# R2020Interface-RS485.net
KiCad netlist of a schematic drawn in EAGLE
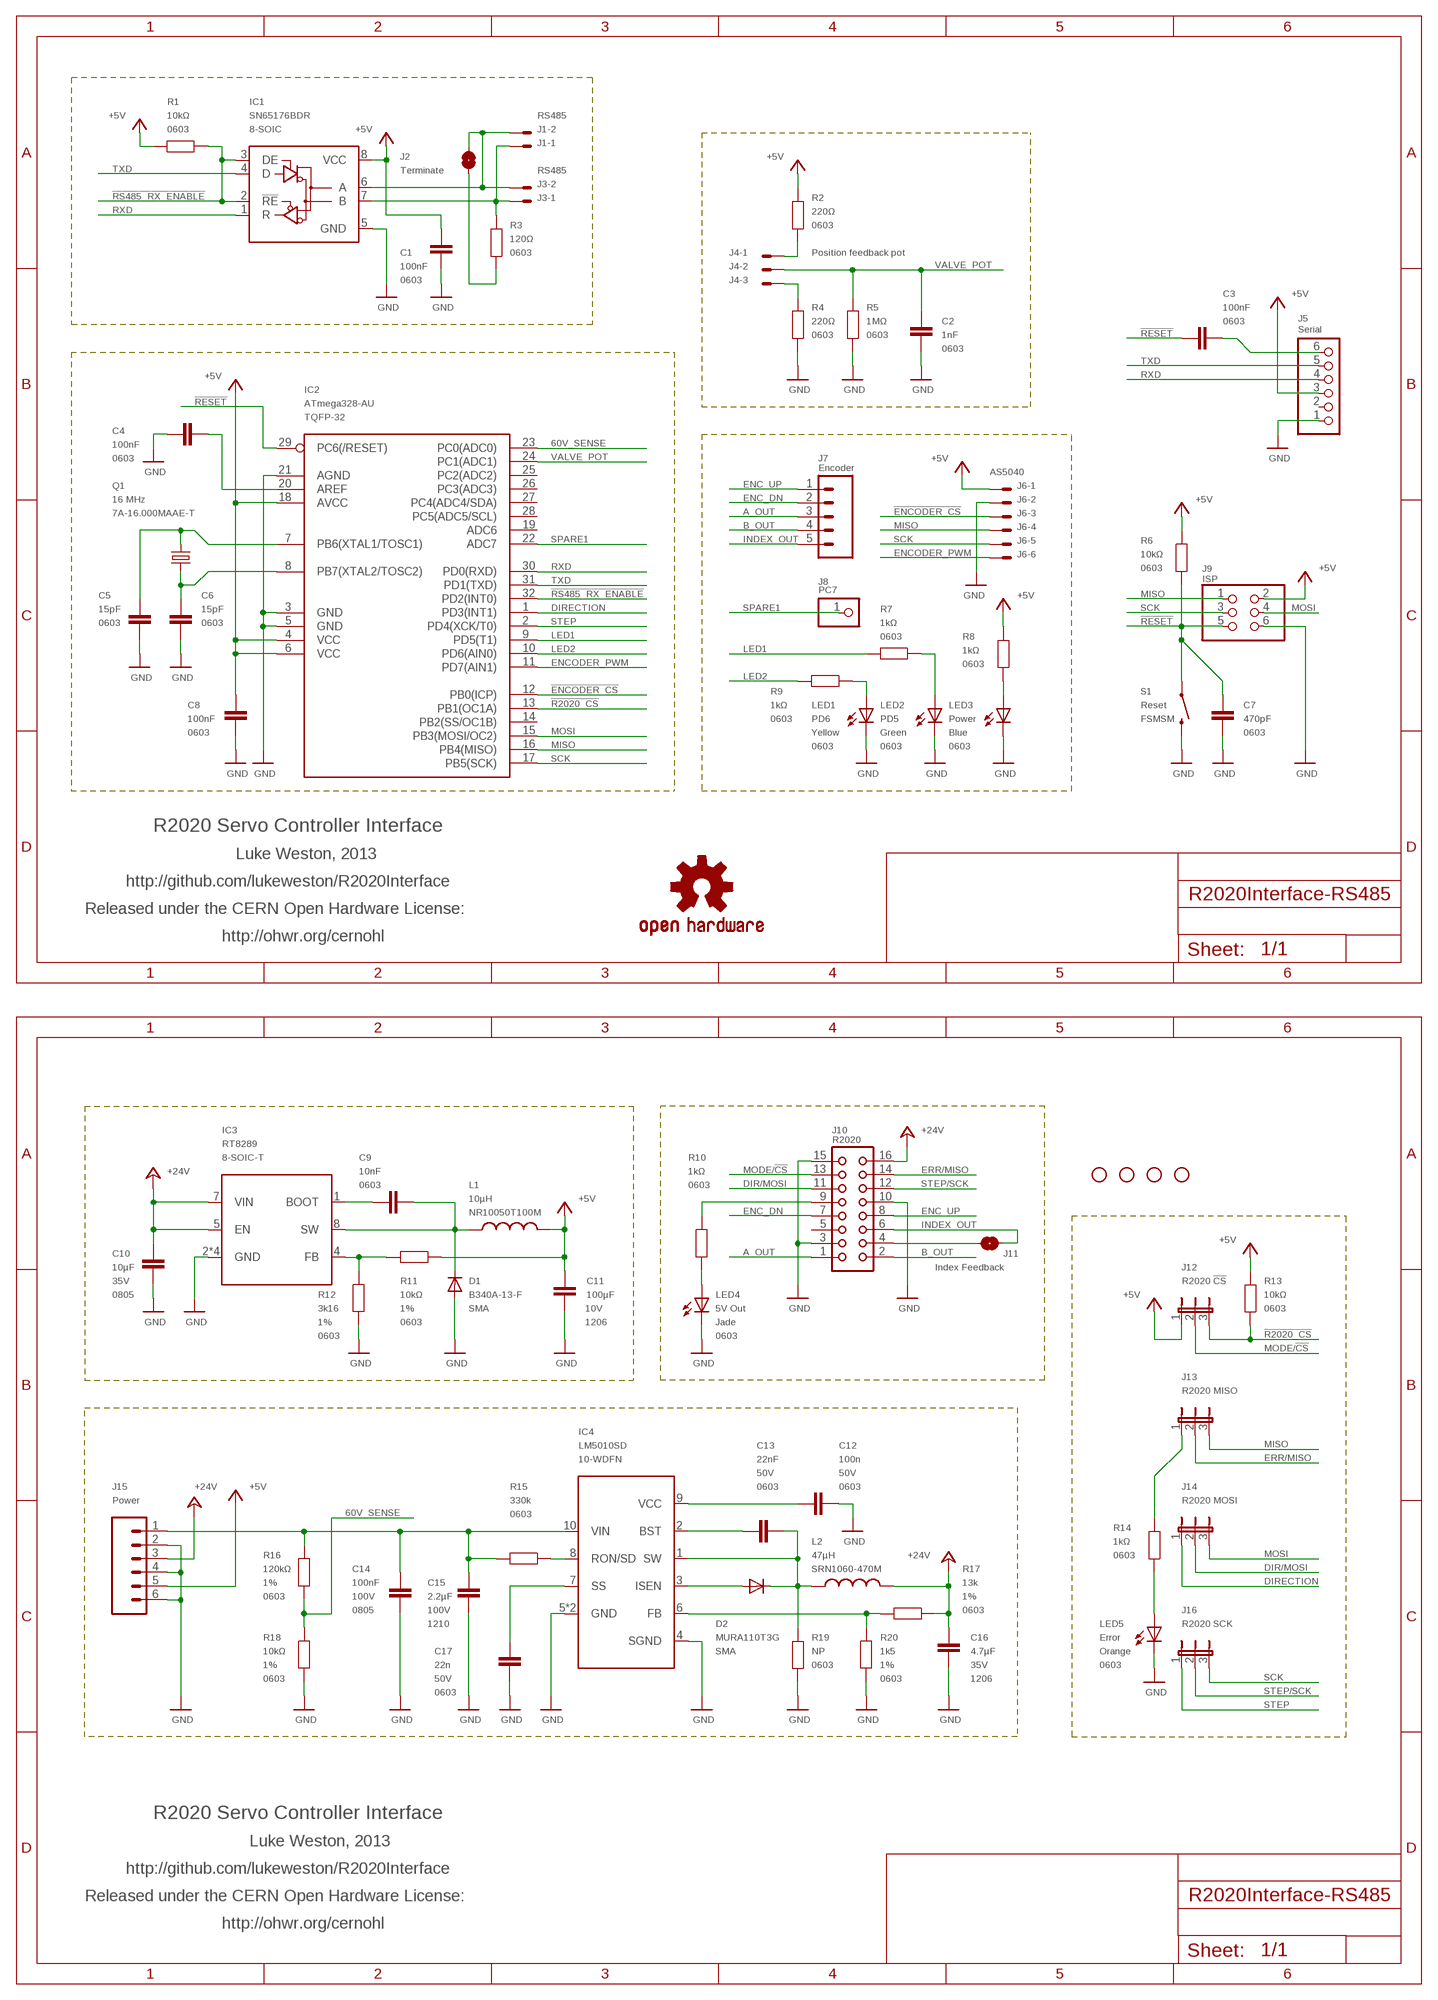
[diagram p0: schematic, sheet 1]

(export (version "E")
  (design (tool "Eeschema 10.0.6"))
  (components
    (comp (ref "C1")
      (value "100nF")
      (footprint "eagle-import:0603")
      (fields (field (name "PACKAGE") "0603"))
      (libsource (lib "eagle-import") (part "CAP0603"))
    )
    (comp (ref "C2")
      (value "1nF")
      (footprint "eagle-import:0603")
      (fields (field (name "PACKAGE") "0603"))
      (libsource (lib "eagle-import") (part "CAP0603"))
    )
    (comp (ref "C3")
      (value "100nF")
      (footprint "eagle-import:0603")
      (fields (field (name "PACKAGE") "0603"))
      (libsource (lib "eagle-import") (part "CAP0603"))
    )
    (comp (ref "C4")
      (value "100nF")
      (footprint "eagle-import:0603")
      (fields (field (name "PACKAGE") "0603"))
      (libsource (lib "eagle-import") (part "CAP0603"))
    )
    (comp (ref "C5")
      (value "15pF")
      (footprint "eagle-import:0603")
      (fields (field (name "PACKAGE") "0603"))
      (libsource (lib "eagle-import") (part "CAP0603"))
    )
    (comp (ref "C6")
      (value "15pF")
      (footprint "eagle-import:0603")
      (fields (field (name "PACKAGE") "0603"))
      (libsource (lib "eagle-import") (part "CAP0603"))
    )
    (comp (ref "C7")
      (value "470pF")
      (footprint "eagle-import:0603")
      (fields (field (name "PACKAGE") "0603"))
      (libsource (lib "eagle-import") (part "CAP0603"))
    )
    (comp (ref "C8")
      (value "100nF")
      (footprint "eagle-import:0603")
      (fields (field (name "PACKAGE") "0603"))
      (libsource (lib "eagle-import") (part "CAP0603"))
    )
    (comp (ref "C9")
      (value "10nF")
      (footprint "eagle-import:0603")
      (fields (field (name "PACKAGE") "0603"))
      (libsource (lib "eagle-import") (part "CAP0603"))
    )
    (comp (ref "C10")
      (value "10µF")
      (footprint "eagle-import:0805")
      (fields (field (name "PACKAGE") "0805") (field (name "VOLTAGE") "35V"))
      (libsource (lib "eagle-import") (part "CAP0805"))
    )
    (comp (ref "C11")
      (value "100µF")
      (footprint "eagle-import:C1206K")
      (fields (field (name "PACKAGE") "1206") (field (name "VOLTAGE") "10V"))
      (libsource (lib "eagle-import") (part "C-EUC1206K"))
    )
    (comp (ref "C12")
      (value "100n")
      (footprint "eagle-import:0603")
      (fields (field (name "PACKAGE") "0603") (field (name "VOLTAGE") "50V"))
      (libsource (lib "eagle-import") (part "CAP0603"))
    )
    (comp (ref "C13")
      (value "22nF")
      (footprint "eagle-import:0603")
      (fields (field (name "PACKAGE") "0603") (field (name "VOLTAGE") "50V"))
      (libsource (lib "eagle-import") (part "CAP0603"))
    )
    (comp (ref "C14")
      (value "100nF")
      (footprint "eagle-import:0805")
      (fields (field (name "PACKAGE") "0805") (field (name "VOLTAGE") "100V"))
      (libsource (lib "eagle-import") (part "CAP0805"))
    )
    (comp (ref "C15")
      (value "2.2µF")
      (footprint "eagle-import:C1210K")
      (fields (field (name "PACKAGE") "1210") (field (name "VOLTAGE") "100V"))
      (libsource (lib "eagle-import") (part "C-EUC1210K"))
    )
    (comp (ref "C16")
      (value "4.7µF")
      (footprint "eagle-import:C1206K")
      (fields (field (name "PACKAGE") "1206") (field (name "VOLTAGE") "35V"))
      (libsource (lib "eagle-import") (part "C-EUC1206K"))
    )
    (comp (ref "C17")
      (value "22n")
      (footprint "eagle-import:0603")
      (fields (field (name "PACKAGE") "0603") (field (name "VOLTAGE") "50V"))
      (libsource (lib "eagle-import") (part "CAP0603"))
    )
    (comp (ref "D1")
      (value "B340A-13-F")
      (footprint "eagle-import:SMA-DIODE")
      (fields (field (name "PACKAGE") "SMA"))
      (libsource (lib "eagle-import") (part "DIODESMA"))
    )
    (comp (ref "D2")
      (value "MURA110T3G")
      (footprint "eagle-import:SMA-DIODE")
      (fields (field (name "PACKAGE") "SMA"))
      (libsource (lib "eagle-import") (part "DIODESMA"))
    )
    (comp (ref "IC1")
      (value "SN65176BDR")
      (footprint "eagle-import:D_R-PDSO-G8")
      (fields (field (name "PACKAGE") "8-SOIC"))
      (libsource (lib "eagle-import") (part "75176AD"))
    )
    (comp (ref "IC2")
      (value "ATmega328-AU")
      (footprint "eagle-import:TQFP32-08")
      (fields (field (name "PACKAGE") "TQFP-32"))
      (libsource (lib "eagle-import") (part "AVR-MEGA8-AI"))
    )
    (comp (ref "IC3")
      (value "RT8289")
      (footprint "eagle-import:SO08T")
      (fields (field (name "PACKAGE") "8-SOIC-T"))
      (libsource (lib "eagle-import") (part "RT8289"))
    )
    (comp (ref "IC4")
      (value "LM5010SD")
      (footprint "eagle-import:10-WSON")
      (fields (field (name "PACKAGE") "10-WDFN"))
      (libsource (lib "eagle-import") (part "LM5010"))
    )
    (comp (ref "J1")
      (value "RS485")
      (footprint "eagle-import:7395-02")
      (libsource (lib "eagle-import") (part "22-?-0205-7028"))
    )
    (comp (ref "J2")
      (value "Terminate")
      (footprint "eagle-import:SJ")
      (libsource (lib "eagle-import") (part "SJ"))
    )
    (comp (ref "J3")
      (value "RS485")
      (footprint "eagle-import:7395-02")
      (fields (field (name "OC_FARNELL") "9731601") (field (name "OC_NEWARK") "unknown"))
      (libsource (lib "eagle-import") (part "22-?-0205-7028"))
    )
    (comp (ref "J4")
      (value "Position feedback pot")
      (footprint "eagle-import:7395-03")
      (libsource (lib "eagle-import") (part "22-?-0305-7038"))
    )
    (comp (ref "J5")
      (value "Serial")
      (footprint "eagle-import:1X06")
      (libsource (lib "eagle-import") (part "PINHD-1X6"))
    )
    (comp (ref "J6")
      (value "AS5040")
      (footprint "eagle-import:7395-06")
      (fields (field (name "OC_FARNELL") "unknown") (field (name "OC_NEWARK") "unknown"))
      (libsource (lib "eagle-import") (part "22-?-0605-7068"))
    )
    (comp (ref "J7")
      (value "Encoder")
      (footprint "eagle-import:1X05")
      (libsource (lib "eagle-import") (part "M05PTH"))
    )
    (comp (ref "J8")
      (value "PC7")
      (footprint "eagle-import:1X01")
      (libsource (lib "eagle-import") (part "PINHD-1X1"))
    )
    (comp (ref "J9")
      (value "ISP")
      (footprint "eagle-import:2X03")
      (libsource (lib "eagle-import") (part "PINHD-2X3"))
    )
    (comp (ref "J10")
      (value "R2020")
      (footprint "eagle-import:CON16")
      (fields (field (name "OC_FARNELL") "unknown") (field (name "OC_NEWARK") "unknown"))
      (libsource (lib "eagle-import") (part "CON16"))
    )
    (comp (ref "J11")
      (value "Index Feedback")
      (footprint "eagle-import:SJ")
      (libsource (lib "eagle-import") (part "SJ"))
    )
    (comp (ref "J12")
      (value "R2020 !CS")
      (footprint "eagle-import:JP2")
      (libsource (lib "eagle-import") (part "JP2E"))
    )
    (comp (ref "J13")
      (value "R2020 MISO")
      (footprint "eagle-import:JP2")
      (libsource (lib "eagle-import") (part "JP2E"))
    )
    (comp (ref "J14")
      (value "R2020 MOSI")
      (footprint "eagle-import:JP2")
      (libsource (lib "eagle-import") (part "JP2E"))
    )
    (comp (ref "J15")
      (value "Power")
      (footprint "eagle-import:TERMINALBLOCK_3.5MM_6")
      (libsource (lib "eagle-import") (part "M06"))
    )
    (comp (ref "J16")
      (value "R2020 SCK")
      (footprint "eagle-import:JP2")
      (libsource (lib "eagle-import") (part "JP2E"))
    )
    (comp (ref "JP1")
      (value "STAND-OFF")
      (footprint "eagle-import:STAND-OFF")
      (libsource (lib "eagle-import") (part "STAND-OFF"))
    )
    (comp (ref "JP2")
      (value "STAND-OFF")
      (footprint "eagle-import:STAND-OFF")
      (libsource (lib "eagle-import") (part "STAND-OFF"))
    )
    (comp (ref "JP3")
      (value "STAND-OFF")
      (footprint "eagle-import:STAND-OFF")
      (libsource (lib "eagle-import") (part "STAND-OFF"))
    )
    (comp (ref "JP4")
      (value "STAND-OFF")
      (footprint "eagle-import:STAND-OFF")
      (libsource (lib "eagle-import") (part "STAND-OFF"))
    )
    (comp (ref "L1")
      (value "10µH")
      (footprint "eagle-import:NR10050")
      (fields (field (name "ID") "NR10050T100M"))
      (libsource (lib "eagle-import") (part "NR10050"))
    )
    (comp (ref "L2")
      (value "47µH")
      (footprint "eagle-import:SRN1060")
      (fields (field (name "ID") "SRN1060-470M"))
      (libsource (lib "eagle-import") (part "SRN1060"))
    )
    (comp (ref "LED1")
      (value "PD6")
      (footprint "eagle-import:LED-0603")
      (fields (field (name "COLOR") "Yellow") (field (name "PACKAGE") "0603"))
      (libsource (lib "eagle-import") (part "LED0603"))
    )
    (comp (ref "LED2")
      (value "PD5")
      (footprint "eagle-import:LED-0603")
      (fields (field (name "COLOR") "Green") (field (name "PACKAGE") "0603"))
      (libsource (lib "eagle-import") (part "LED0603"))
    )
    (comp (ref "LED3")
      (value "Power")
      (footprint "eagle-import:LED-0603")
      (fields (field (name "COLOR") "Blue") (field (name "PACKAGE") "0603"))
      (libsource (lib "eagle-import") (part "LED0603"))
    )
    (comp (ref "LED4")
      (value "5V Out")
      (footprint "eagle-import:LED-0603")
      (fields (field (name "COLOR") "Jade") (field (name "PACKAGE") "0603"))
      (libsource (lib "eagle-import") (part "LED0603"))
    )
    (comp (ref "LED5")
      (value "Error")
      (footprint "eagle-import:LED-0603")
      (fields (field (name "COLOR") "Orange") (field (name "PACKAGE") "0603"))
      (libsource (lib "eagle-import") (part "LED0603"))
    )
    (comp (ref "Q1")
      (value "16 MHz")
      (footprint "eagle-import:CRYSTAL-3.2X5MM")
      (fields (field (name "ID") "7A-16.000MAAE-T"))
      (libsource (lib "eagle-import") (part "CRYSTAL-2LEAD3.2X5"))
    )
    (comp (ref "R1")
      (value "10kΩ")
      (footprint "eagle-import:0603")
      (fields (field (name "PACKAGE") "0603"))
      (libsource (lib "eagle-import") (part "RESISTOR0603"))
    )
    (comp (ref "R2")
      (value "220Ω")
      (footprint "eagle-import:0603")
      (fields (field (name "PACKAGE") "0603"))
      (libsource (lib "eagle-import") (part "RESISTOR0603"))
    )
    (comp (ref "R3")
      (value "120Ω")
      (footprint "eagle-import:0603")
      (fields (field (name "PACKAGE") "0603"))
      (libsource (lib "eagle-import") (part "RESISTOR0603"))
    )
    (comp (ref "R4")
      (value "220Ω")
      (footprint "eagle-import:0603")
      (fields (field (name "PACKAGE") "0603"))
      (libsource (lib "eagle-import") (part "RESISTOR0603"))
    )
    (comp (ref "R5")
      (value "1MΩ")
      (footprint "eagle-import:0603")
      (fields (field (name "PACKAGE") "0603"))
      (libsource (lib "eagle-import") (part "RESISTOR0603"))
    )
    (comp (ref "R6")
      (value "10kΩ")
      (footprint "eagle-import:0603")
      (fields (field (name "PACKAGE") "0603"))
      (libsource (lib "eagle-import") (part "RESISTOR0603"))
    )
    (comp (ref "R7")
      (value "1kΩ")
      (footprint "eagle-import:0603")
      (fields (field (name "PACKAGE") "0603"))
      (libsource (lib "eagle-import") (part "RESISTOR0603"))
    )
    (comp (ref "R8")
      (value "1kΩ")
      (footprint "eagle-import:0603")
      (fields (field (name "PACKAGE") "0603"))
      (libsource (lib "eagle-import") (part "RESISTOR0603"))
    )
    (comp (ref "R9")
      (value "1kΩ")
      (footprint "eagle-import:0603")
      (fields (field (name "PACKAGE") "0603"))
      (libsource (lib "eagle-import") (part "RESISTOR0603"))
    )
    (comp (ref "R10")
      (value "1kΩ")
      (footprint "eagle-import:0603")
      (fields (field (name "PACKAGE") "0603"))
      (libsource (lib "eagle-import") (part "RESISTOR0603"))
    )
    (comp (ref "R11")
      (value "10kΩ")
      (footprint "eagle-import:0603")
      (fields (field (name "PACKAGE") "0603") (field (name "TOLERANCE") "1%"))
      (libsource (lib "eagle-import") (part "RESISTOR0603"))
    )
    (comp (ref "R12")
      (value "3k16")
      (footprint "eagle-import:0603")
      (fields (field (name "PACKAGE") "0603") (field (name "TOLERANCE") "1%"))
      (libsource (lib "eagle-import") (part "RESISTOR0603"))
    )
    (comp (ref "R13")
      (value "10kΩ")
      (footprint "eagle-import:0603")
      (fields (field (name "PACKAGE") "0603"))
      (libsource (lib "eagle-import") (part "RESISTOR0603"))
    )
    (comp (ref "R14")
      (value "1kΩ")
      (footprint "eagle-import:0603")
      (fields (field (name "PACKAGE") "0603"))
      (libsource (lib "eagle-import") (part "RESISTOR0603"))
    )
    (comp (ref "R15")
      (value "330k")
      (footprint "eagle-import:0603")
      (fields (field (name "PACKAGE") "0603"))
      (libsource (lib "eagle-import") (part "RESISTOR0603"))
    )
    (comp (ref "R16")
      (value "120kΩ")
      (footprint "eagle-import:0603")
      (fields (field (name "PACKAGE") "0603") (field (name "TOLERANCE") "1%"))
      (libsource (lib "eagle-import") (part "RESISTOR0603"))
    )
    (comp (ref "R17")
      (value "13k")
      (footprint "eagle-import:0603")
      (fields (field (name "PACKAGE") "0603") (field (name "TOLERANCE") "1%"))
      (libsource (lib "eagle-import") (part "RESISTOR0603"))
    )
    (comp (ref "R18")
      (value "10kΩ")
      (footprint "eagle-import:0603")
      (fields (field (name "PACKAGE") "0603") (field (name "TOLERANCE") "1%"))
      (libsource (lib "eagle-import") (part "RESISTOR0603"))
    )
    (comp (ref "R19")
      (value "NP")
      (footprint "eagle-import:0603")
      (fields (field (name "PACKAGE") "0603"))
      (libsource (lib "eagle-import") (part "RESISTOR0603"))
    )
    (comp (ref "R20")
      (value "1k5")
      (footprint "eagle-import:0603")
      (fields (field (name "PACKAGE") "0603") (field (name "TOLERANCE") "1%"))
      (libsource (lib "eagle-import") (part "RESISTOR0603"))
    )
    (comp (ref "S1")
      (value "Reset")
      (footprint "eagle-import:FSMSM")
      (fields (field (name "PACKAGE") "FSMSM"))
      (libsource (lib "eagle-import") (part "FSMSM"))
    )
    (comp (ref "SY1")
      (value "OSHW-LOGOS")
      (footprint "eagle-import:OSHW-LOGO-S")
      (libsource (lib "eagle-import") (part "OSHW-LOGOS"))
    )
  )
  (nets
    (net (code "1") (name "+5V") (class "Default")
      (node (ref "C1") (pin "2") (pinfunction "2_2") (pintype "passive"))
      (node (ref "C11") (pin "1") (pinfunction "1_1") (pintype "passive"))
      (node (ref "C8") (pin "1") (pinfunction "1_1") (pintype "passive"))
      (node (ref "IC1") (pin "8") (pinfunction "VCC_8") (pintype "power_in"))
      (node (ref "IC2") (pin "18") (pinfunction "AVCC_18") (pintype "bidirectional"))
      (node (ref "IC2") (pin "4") (pinfunction "VCC_4") (pintype "bidirectional"))
      (node (ref "IC2") (pin "6") (pinfunction "VCC_6") (pintype "bidirectional"))
      (node (ref "J12") (pin "1") (pinfunction "1_1") (pintype "passive"))
      (node (ref "J15") (pin "5") (pinfunction "5_5") (pintype "passive"))
      (node (ref "J5") (pin "3") (pinfunction "3_3") (pintype "passive"))
      (node (ref "J6") (pin "1") (pinfunction "S_1") (pintype "passive"))
      (node (ref "J9") (pin "2") (pinfunction "2_2") (pintype "passive"))
      (node (ref "L1") (pin "2") (pinfunction "2_2") (pintype "bidirectional"))
      (node (ref "R1") (pin "1") (pinfunction "1_1") (pintype "passive"))
      (node (ref "R11") (pin "1") (pinfunction "1_1") (pintype "passive"))
      (node (ref "R13") (pin "1") (pinfunction "1_1") (pintype "passive"))
      (node (ref "R2") (pin "1") (pinfunction "1_1") (pintype "passive"))
      (node (ref "R6") (pin "2") (pinfunction "2_2") (pintype "passive"))
      (node (ref "R8") (pin "1") (pinfunction "1_1") (pintype "passive"))
    )
    (net (code "2") (name "+24V") (class "Default")
      (node (ref "C10") (pin "2") (pinfunction "2_2") (pintype "passive"))
      (node (ref "C16") (pin "1") (pinfunction "1_1") (pintype "passive"))
      (node (ref "IC3") (pin "5") (pinfunction "EN_5") (pintype "bidirectional"))
      (node (ref "IC3") (pin "7") (pinfunction "VIN_7") (pintype "bidirectional"))
      (node (ref "J10") (pin "16") (pinfunction "16_16") (pintype "passive"))
      (node (ref "J15") (pin "3") (pinfunction "3_3") (pintype "passive"))
      (node (ref "L2") (pin "2") (pinfunction "2_2") (pintype "bidirectional"))
      (node (ref "R17") (pin "1") (pinfunction "1_1") (pintype "passive"))
    )
    (net (code "3") (name "/60V_SENSE") (class "Default")
      (node (ref "IC2") (pin "23") (pinfunction "PC0(ADC0)_23") (pintype "bidirectional"))
      (node (ref "R16") (pin "1") (pinfunction "1_1") (pintype "passive"))
      (node (ref "R18") (pin "2") (pinfunction "2_2") (pintype "passive"))
    )
    (net (code "4") (name "/A_OUT") (class "Default")
      (node (ref "J10") (pin "1") (pinfunction "1_1") (pintype "passive"))
      (node (ref "J7") (pin "3") (pinfunction "3_3") (pintype "passive"))
    )
    (net (code "5") (name "/B_OUT") (class "Default")
      (node (ref "J10") (pin "2") (pinfunction "2_2") (pintype "passive"))
      (node (ref "J7") (pin "4") (pinfunction "4_4") (pintype "passive"))
    )
    (net (code "6") (name "/DIRECTION") (class "Default")
      (node (ref "IC2") (pin "1") (pinfunction "PD3(INT1)_1") (pintype "bidirectional"))
      (node (ref "J14") (pin "1") (pinfunction "1_1") (pintype "passive"))
    )
    (net (code "7") (name "/DIR{slash}MOSI") (class "Default")
      (node (ref "J10") (pin "11") (pinfunction "11_11") (pintype "passive"))
      (node (ref "J14") (pin "2") (pinfunction "2_2") (pintype "passive"))
    )
    (net (code "8") (name "/ENCODER_PWM") (class "Default")
      (node (ref "IC2") (pin "11") (pinfunction "PD7(AIN1)_11") (pintype "bidirectional"))
      (node (ref "J6") (pin "6") (pinfunction "S_6") (pintype "passive"))
    )
    (net (code "9") (name "/ENC_DN") (class "Default")
      (node (ref "J10") (pin "7") (pinfunction "7_7") (pintype "passive"))
      (node (ref "J7") (pin "2") (pinfunction "2_2") (pintype "passive"))
    )
    (net (code "10") (name "/ENC_UP") (class "Default")
      (node (ref "J10") (pin "8") (pinfunction "8_8") (pintype "passive"))
      (node (ref "J7") (pin "1") (pinfunction "1_1") (pintype "passive"))
    )
    (net (code "11") (name "/ERR{slash}MISO") (class "Default")
      (node (ref "J10") (pin "14") (pinfunction "14_14") (pintype "passive"))
      (node (ref "J13") (pin "2") (pinfunction "2_2") (pintype "passive"))
    )
    (net (code "12") (name "/INDEX_OUT") (class "Default")
      (node (ref "J10") (pin "6") (pinfunction "6_6") (pintype "passive"))
      (node (ref "J11") (pin "1") (pinfunction "1_1") (pintype "passive"))
      (node (ref "J7") (pin "5") (pinfunction "5_5") (pintype "passive"))
    )
    (net (code "13") (name "/LED1") (class "Default")
      (node (ref "IC2") (pin "9") (pinfunction "PD5(T1)_9") (pintype "bidirectional"))
      (node (ref "R7") (pin "2") (pinfunction "2_2") (pintype "passive"))
    )
    (net (code "14") (name "/LED2") (class "Default")
      (node (ref "IC2") (pin "10") (pinfunction "PD6(AIN0)_10") (pintype "bidirectional"))
      (node (ref "R9") (pin "2") (pinfunction "2_2") (pintype "passive"))
    )
    (net (code "15") (name "/MISO") (class "Default")
      (node (ref "IC2") (pin "16") (pinfunction "PB4(MISO)_16") (pintype "bidirectional"))
      (node (ref "J13") (pin "3") (pinfunction "3_3") (pintype "passive"))
      (node (ref "J6") (pin "4") (pinfunction "S_4") (pintype "passive"))
      (node (ref "J9") (pin "1") (pinfunction "1_1") (pintype "passive"))
    )
    (net (code "16") (name "/MODE{slash}~{CS}") (class "Default")
      (node (ref "J10") (pin "13") (pinfunction "13_13") (pintype "passive"))
      (node (ref "J12") (pin "2") (pinfunction "2_2") (pintype "passive"))
    )
    (net (code "17") (name "/MOSI") (class "Default")
      (node (ref "IC2") (pin "15") (pinfunction "PB3(MOSI/OC2)_15") (pintype "bidirectional"))
      (node (ref "J14") (pin "3") (pinfunction "3_3") (pintype "passive"))
      (node (ref "J9") (pin "4") (pinfunction "4_4") (pintype "passive"))
    )
    (net (code "18") (name "/RXD") (class "Default")
      (node (ref "IC1") (pin "1") (pinfunction "R_1") (pintype "input"))
      (node (ref "IC2") (pin "30") (pinfunction "PD0(RXD)_30") (pintype "bidirectional"))
      (node (ref "J5") (pin "4") (pinfunction "4_4") (pintype "passive"))
    )
    (net (code "19") (name "/SCK") (class "Default")
      (node (ref "IC2") (pin "17") (pinfunction "PB5(SCK)_17") (pintype "bidirectional"))
      (node (ref "J16") (pin "3") (pinfunction "3_3") (pintype "passive"))
      (node (ref "J6") (pin "5") (pinfunction "S_5") (pintype "passive"))
      (node (ref "J9") (pin "3") (pinfunction "3_3") (pintype "passive"))
    )
    (net (code "20") (name "/SPARE1") (class "Default")
      (node (ref "IC2") (pin "22") (pinfunction "ADC7_22") (pintype "bidirectional"))
      (node (ref "J8") (pin "1") (pinfunction "1_1") (pintype "passive"))
    )
    (net (code "21") (name "/STEP") (class "Default")
      (node (ref "IC2") (pin "2") (pinfunction "PD4(XCK/T0)_2") (pintype "bidirectional"))
      (node (ref "J16") (pin "1") (pinfunction "1_1") (pintype "passive"))
    )
    (net (code "22") (name "/STEP{slash}SCK") (class "Default")
      (node (ref "J10") (pin "12") (pinfunction "12_12") (pintype "passive"))
      (node (ref "J16") (pin "2") (pinfunction "2_2") (pintype "passive"))
    )
    (net (code "23") (name "/TXD") (class "Default")
      (node (ref "IC1") (pin "4") (pinfunction "D_4") (pintype "input"))
      (node (ref "IC2") (pin "31") (pinfunction "PD1(TXD)_31") (pintype "bidirectional"))
      (node (ref "J5") (pin "5") (pinfunction "5_5") (pintype "passive"))
    )
    (net (code "24") (name "/VALVE_POT") (class "Default")
      (node (ref "C2") (pin "2") (pinfunction "2_2") (pintype "passive"))
      (node (ref "IC2") (pin "24") (pinfunction "PC1(ADC1)_24") (pintype "bidirectional"))
      (node (ref "J4") (pin "2") (pinfunction "S_2") (pintype "passive"))
      (node (ref "R5") (pin "1") (pinfunction "1_1") (pintype "passive"))
    )
    (net (code "25") (name "/~{ENCODER_CS}") (class "Default")
      (node (ref "IC2") (pin "12") (pinfunction "PB0(ICP)_12") (pintype "bidirectional"))
      (node (ref "J6") (pin "3") (pinfunction "S_3") (pintype "passive"))
    )
    (net (code "26") (name "/~{R2020_CS}") (class "Default")
      (node (ref "IC2") (pin "13") (pinfunction "PB1(OC1A)_13") (pintype "bidirectional"))
      (node (ref "J12") (pin "3") (pinfunction "3_3") (pintype "passive"))
      (node (ref "R13") (pin "2") (pinfunction "2_2") (pintype "passive"))
    )
    (net (code "27") (name "/~{RESET}") (class "Default")
      (node (ref "C3") (pin "1") (pinfunction "1_1") (pintype "passive"))
      (node (ref "C7") (pin "2") (pinfunction "2_2") (pintype "passive"))
      (node (ref "IC2") (pin "29") (pinfunction "PC6(/RESET)_29") (pintype "bidirectional"))
      (node (ref "J9") (pin "5") (pinfunction "5_5") (pintype "passive"))
      (node (ref "R6") (pin "1") (pinfunction "1_1") (pintype "passive"))
      (node (ref "S1") (pin "1") (pinfunction "1_1") (pintype "passive"))
    )
    (net (code "28") (name "/~{RS485_RX_ENABLE}") (class "Default")
      (node (ref "IC1") (pin "2") (pinfunction "~{RE}_2") (pintype "input"))
      (node (ref "IC1") (pin "3") (pinfunction "DE_3") (pintype "input"))
      (node (ref "IC2") (pin "32") (pinfunction "PD2(INT0)_32") (pintype "bidirectional"))
      (node (ref "R1") (pin "2") (pinfunction "2_2") (pintype "passive"))
    )
    (net (code "29") (name "GND") (class "Default")
      (node (ref "C1") (pin "1") (pinfunction "1_1") (pintype "passive"))
      (node (ref "C10") (pin "1") (pinfunction "1_1") (pintype "passive"))
      (node (ref "C11") (pin "2") (pinfunction "2_2") (pintype "passive"))
      (node (ref "C12") (pin "1") (pinfunction "1_1") (pintype "passive"))
      (node (ref "C14") (pin "1") (pinfunction "1_1") (pintype "passive"))
      (node (ref "C15") (pin "2") (pinfunction "2_2") (pintype "passive"))
      (node (ref "C16") (pin "2") (pinfunction "2_2") (pintype "passive"))
      (node (ref "C17") (pin "1") (pinfunction "1_1") (pintype "passive"))
      (node (ref "C2") (pin "1") (pinfunction "1_1") (pintype "passive"))
      (node (ref "C4") (pin "2") (pinfunction "2_2") (pintype "passive"))
      (node (ref "C5") (pin "1") (pinfunction "1_1") (pintype "passive"))
      (node (ref "C6") (pin "1") (pinfunction "1_1") (pintype "passive"))
      (node (ref "C7") (pin "1") (pinfunction "1_1") (pintype "passive"))
      (node (ref "C8") (pin "2") (pinfunction "2_2") (pintype "passive"))
      (node (ref "D1") (pin "A") (pinfunction "A_A") (pintype "passive"))
      (node (ref "IC1") (pin "5") (pinfunction "GND_5") (pintype "power_in"))
      (node (ref "IC2") (pin "21") (pinfunction "AGND_21") (pintype "bidirectional"))
      (node (ref "IC2") (pin "3") (pinfunction "GND_3") (pintype "bidirectional"))
      (node (ref "IC2") (pin "5") (pinfunction "GND_5") (pintype "bidirectional"))
      (node (ref "IC3") (pin "2") (pinfunction "GND_2") (pintype "bidirectional"))
      (node (ref "IC3") (pin "3") (pinfunction "GND_3") (pintype "bidirectional"))
      (node (ref "IC3") (pin "6") (pinfunction "GND_6") (pintype "bidirectional"))
      (node (ref "IC3") (pin "PAD") (pinfunction "GND_PAD") (pintype "bidirectional"))
      (node (ref "IC4") (pin "4") (pinfunction "SGND_4") (pintype "bidirectional"))
      (node (ref "IC4") (pin "5") (pinfunction "GND_5") (pintype "bidirectional"))
      (node (ref "IC4") (pin "PAD") (pinfunction "GND_PAD") (pintype "bidirectional"))
      (node (ref "J10") (pin "10") (pinfunction "10_10") (pintype "passive"))
      (node (ref "J10") (pin "15") (pinfunction "15_15") (pintype "passive"))
      (node (ref "J10") (pin "3") (pinfunction "3_3") (pintype "passive"))
      (node (ref "J15") (pin "2") (pinfunction "2_2") (pintype "passive"))
      (node (ref "J15") (pin "4") (pinfunction "4_4") (pintype "passive"))
      (node (ref "J15") (pin "6") (pinfunction "6_6") (pintype "passive"))
      (node (ref "J5") (pin "1") (pinfunction "1_1") (pintype "passive"))
      (node (ref "J6") (pin "2") (pinfunction "S_2") (pintype "passive"))
      (node (ref "J9") (pin "6") (pinfunction "6_6") (pintype "passive"))
      (node (ref "LED1") (pin "C") (pinfunction "C_C") (pintype "passive"))
      (node (ref "LED2") (pin "C") (pinfunction "C_C") (pintype "passive"))
      (node (ref "LED3") (pin "C") (pinfunction "C_C") (pintype "passive"))
      (node (ref "LED4") (pin "C") (pinfunction "C_C") (pintype "passive"))
      (node (ref "LED5") (pin "C") (pinfunction "C_C") (pintype "passive"))
      (node (ref "R12") (pin "1") (pinfunction "1_1") (pintype "passive"))
      (node (ref "R18") (pin "1") (pinfunction "1_1") (pintype "passive"))
      (node (ref "R19") (pin "2") (pinfunction "2_2") (pintype "passive"))
      (node (ref "R20") (pin "1") (pinfunction "1_1") (pintype "passive"))
      (node (ref "R4") (pin "2") (pinfunction "2_2") (pintype "passive"))
      (node (ref "R5") (pin "2") (pinfunction "2_2") (pintype "passive"))
      (node (ref "S1") (pin "2") (pinfunction "2_2") (pintype "passive"))
    )
    (net (code "30") (name "Net-(C3-Pad2)") (class "Default")
      (node (ref "C3") (pin "2") (pinfunction "2_2") (pintype "passive"))
      (node (ref "J5") (pin "6") (pinfunction "6_6") (pintype "passive"))
    )
    (net (code "31") (name "Net-(IC1-A)") (class "Default")
      (node (ref "IC1") (pin "6") (pinfunction "A_6") (pintype "output"))
      (node (ref "J1") (pin "2") (pinfunction "S_2") (pintype "passive"))
      (node (ref "J2") (pin "2") (pinfunction "2_2") (pintype "passive"))
      (node (ref "J3") (pin "2") (pinfunction "S_2") (pintype "passive"))
    )
    (net (code "32") (name "Net-(IC1-B)") (class "Default")
      (node (ref "IC1") (pin "7") (pinfunction "B_7") (pintype "output"))
      (node (ref "J1") (pin "1") (pinfunction "S_1") (pintype "passive"))
      (node (ref "J3") (pin "1") (pinfunction "S_1") (pintype "passive"))
      (node (ref "R3") (pin "1") (pinfunction "1_1") (pintype "passive"))
    )
    (net (code "33") (name "Net-(IC2-AREF)") (class "Default")
      (node (ref "C4") (pin "1") (pinfunction "1_1") (pintype "passive"))
      (node (ref "IC2") (pin "20") (pinfunction "AREF_20") (pintype "bidirectional"))
    )
    (net (code "34") (name "Net-(IC2-PB6(XTAL1{slash}TOSC1))") (class "Default")
      (node (ref "C5") (pin "2") (pinfunction "2_2") (pintype "passive"))
      (node (ref "IC2") (pin "7") (pinfunction "PB6(XTAL1/TOSC1)_7") (pintype "bidirectional"))
      (node (ref "Q1") (pin "1") (pinfunction "1_1") (pintype "bidirectional"))
    )
    (net (code "35") (name "Net-(IC2-PB7(XTAL2{slash}TOSC2))") (class "Default")
      (node (ref "C6") (pin "2") (pinfunction "2_2") (pintype "passive"))
      (node (ref "IC2") (pin "8") (pinfunction "PB7(XTAL2/TOSC2)_8") (pintype "bidirectional"))
      (node (ref "Q1") (pin "2") (pinfunction "2_2") (pintype "bidirectional"))
    )
    (net (code "36") (name "Net-(IC3-BOOT)") (class "Default")
      (node (ref "C9") (pin "2") (pinfunction "2_2") (pintype "passive"))
      (node (ref "IC3") (pin "1") (pinfunction "BOOT_1") (pintype "bidirectional"))
    )
    (net (code "37") (name "Net-(IC3-FB)") (class "Default")
      (node (ref "IC3") (pin "4") (pinfunction "FB_4") (pintype "bidirectional"))
      (node (ref "R11") (pin "2") (pinfunction "2_2") (pintype "passive"))
      (node (ref "R12") (pin "2") (pinfunction "2_2") (pintype "passive"))
    )
    (net (code "38") (name "Net-(IC3-SW)") (class "Default")
      (node (ref "C9") (pin "1") (pinfunction "1_1") (pintype "passive"))
      (node (ref "D1") (pin "C") (pinfunction "C_C") (pintype "passive"))
      (node (ref "IC3") (pin "8") (pinfunction "SW_8") (pintype "bidirectional"))
      (node (ref "L1") (pin "1") (pinfunction "1_1") (pintype "bidirectional"))
    )
    (net (code "39") (name "Net-(IC4-BST)") (class "Default")
      (node (ref "C13") (pin "2") (pinfunction "2_2") (pintype "passive"))
      (node (ref "IC4") (pin "2") (pinfunction "BST_2") (pintype "bidirectional"))
    )
    (net (code "40") (name "Net-(IC4-FB)") (class "Default")
      (node (ref "IC4") (pin "6") (pinfunction "FB_6") (pintype "bidirectional"))
      (node (ref "R17") (pin "2") (pinfunction "2_2") (pintype "passive"))
      (node (ref "R20") (pin "2") (pinfunction "2_2") (pintype "passive"))
    )
    (net (code "41") (name "Net-(IC4-ISEN)") (class "Default")
      (node (ref "D2") (pin "A") (pinfunction "A_A") (pintype "passive"))
      (node (ref "IC4") (pin "3") (pinfunction "ISEN_3") (pintype "bidirectional"))
    )
    (net (code "42") (name "Net-(IC4-RON{slash}SD)") (class "Default")
      (node (ref "IC4") (pin "8") (pinfunction "RON/SD_8") (pintype "bidirectional"))
      (node (ref "R15") (pin "1") (pinfunction "1_1") (pintype "passive"))
    )
    (net (code "43") (name "Net-(IC4-SS)") (class "Default")
      (node (ref "C17") (pin "2") (pinfunction "2_2") (pintype "passive"))
      (node (ref "IC4") (pin "7") (pinfunction "SS_7") (pintype "bidirectional"))
    )
    (net (code "44") (name "Net-(IC4-SW)") (class "Default")
      (node (ref "C13") (pin "1") (pinfunction "1_1") (pintype "passive"))
      (node (ref "D2") (pin "C") (pinfunction "C_C") (pintype "passive"))
      (node (ref "IC4") (pin "1") (pinfunction "SW_1") (pintype "bidirectional"))
      (node (ref "L2") (pin "1") (pinfunction "1_1") (pintype "bidirectional"))
      (node (ref "R19") (pin "1") (pinfunction "1_1") (pintype "passive"))
    )
    (net (code "45") (name "Net-(IC4-VCC)") (class "Default")
      (node (ref "C12") (pin "2") (pinfunction "2_2") (pintype "passive"))
      (node (ref "IC4") (pin "9") (pinfunction "VCC_9") (pintype "bidirectional"))
    )
    (net (code "46") (name "Net-(IC4-VIN)") (class "Default")
      (node (ref "C14") (pin "2") (pinfunction "2_2") (pintype "passive"))
      (node (ref "C15") (pin "1") (pinfunction "1_1") (pintype "passive"))
      (node (ref "IC4") (pin "10") (pinfunction "VIN_10") (pintype "bidirectional"))
      (node (ref "J15") (pin "1") (pinfunction "1_1") (pintype "passive"))
      (node (ref "R15") (pin "2") (pinfunction "2_2") (pintype "passive"))
      (node (ref "R16") (pin "2") (pinfunction "2_2") (pintype "passive"))
    )
    (net (code "47") (name "Net-(J2-Pad1)") (class "Default")
      (node (ref "J2") (pin "1") (pinfunction "1_1") (pintype "passive"))
      (node (ref "R3") (pin "2") (pinfunction "2_2") (pintype "passive"))
    )
    (net (code "48") (name "Net-(J4A-S)") (class "Default")
      (node (ref "J4") (pin "1") (pinfunction "S_1") (pintype "passive"))
      (node (ref "R2") (pin "2") (pinfunction "2_2") (pintype "passive"))
    )
    (net (code "49") (name "Net-(J4C-S)") (class "Default")
      (node (ref "J4") (pin "3") (pinfunction "S_3") (pintype "passive"))
      (node (ref "R4") (pin "1") (pinfunction "1_1") (pintype "passive"))
    )
    (net (code "50") (name "Net-(J10-Pad4)") (class "Default")
      (node (ref "J10") (pin "4") (pinfunction "4_4") (pintype "passive"))
      (node (ref "J11") (pin "2") (pinfunction "2_2") (pintype "passive"))
    )
    (net (code "51") (name "Net-(J10-Pad9)") (class "Default")
      (node (ref "J10") (pin "9") (pinfunction "9_9") (pintype "passive"))
      (node (ref "R10") (pin "2") (pinfunction "2_2") (pintype "passive"))
    )
    (net (code "52") (name "Net-(J13-Pad1)") (class "Default")
      (node (ref "J13") (pin "1") (pinfunction "1_1") (pintype "passive"))
      (node (ref "R14") (pin "1") (pinfunction "1_1") (pintype "passive"))
    )
    (net (code "53") (name "Net-(LED1-PadA)") (class "Default")
      (node (ref "LED1") (pin "A") (pinfunction "A_A") (pintype "passive"))
      (node (ref "R9") (pin "1") (pinfunction "1_1") (pintype "passive"))
    )
    (net (code "54") (name "Net-(LED2-PadA)") (class "Default")
      (node (ref "LED2") (pin "A") (pinfunction "A_A") (pintype "passive"))
      (node (ref "R7") (pin "1") (pinfunction "1_1") (pintype "passive"))
    )
    (net (code "55") (name "Net-(LED3-PadA)") (class "Default")
      (node (ref "LED3") (pin "A") (pinfunction "A_A") (pintype "passive"))
      (node (ref "R8") (pin "2") (pinfunction "2_2") (pintype "passive"))
    )
    (net (code "56") (name "Net-(LED4-PadA)") (class "Default")
      (node (ref "LED4") (pin "A") (pinfunction "A_A") (pintype "passive"))
      (node (ref "R10") (pin "1") (pinfunction "1_1") (pintype "passive"))
    )
    (net (code "57") (name "Net-(LED5-PadA)") (class "Default")
      (node (ref "LED5") (pin "A") (pinfunction "A_A") (pintype "passive"))
      (node (ref "R14") (pin "2") (pinfunction "2_2") (pintype "passive"))
    )
    (net (code "58") (name "unconnected-(IC2-ADC6-Pad19)") (class "Default")
      (node (ref "IC2") (pin "19") (pinfunction "ADC6_19") (pintype "bidirectional"))
    )
    (net (code "59") (name "unconnected-(IC2-PB2(SS{slash}OC1B)-Pad14)") (class "Default")
      (node (ref "IC2") (pin "14") (pinfunction "PB2(SS/OC1B)_14") (pintype "bidirectional"))
    )
    (net (code "60") (name "unconnected-(IC2-PC2(ADC2)-Pad25)") (class "Default")
      (node (ref "IC2") (pin "25") (pinfunction "PC2(ADC2)_25") (pintype "bidirectional"))
    )
    (net (code "61") (name "unconnected-(IC2-PC3(ADC3)-Pad26)") (class "Default")
      (node (ref "IC2") (pin "26") (pinfunction "PC3(ADC3)_26") (pintype "bidirectional"))
    )
    (net (code "62") (name "unconnected-(IC2-PC4(ADC4{slash}SDA)-Pad27)") (class "Default")
      (node (ref "IC2") (pin "27") (pinfunction "PC4(ADC4/SDA)_27") (pintype "bidirectional"))
    )
    (net (code "63") (name "unconnected-(IC2-PC5(ADC5{slash}SCL)-Pad28)") (class "Default")
      (node (ref "IC2") (pin "28") (pinfunction "PC5(ADC5/SCL)_28") (pintype "bidirectional"))
    )
    (net (code "64") (name "unconnected-(J5-Pad2)") (class "Default")
      (node (ref "J5") (pin "2") (pinfunction "2_2") (pintype "passive"))
    )
    (net (code "65") (name "unconnected-(J10-Pad5)") (class "Default")
      (node (ref "J10") (pin "5") (pinfunction "5_5") (pintype "passive"))
    )
  )
)
